# Sheet1.net
KiCad netlist of a schematic drawn in Altium Designer
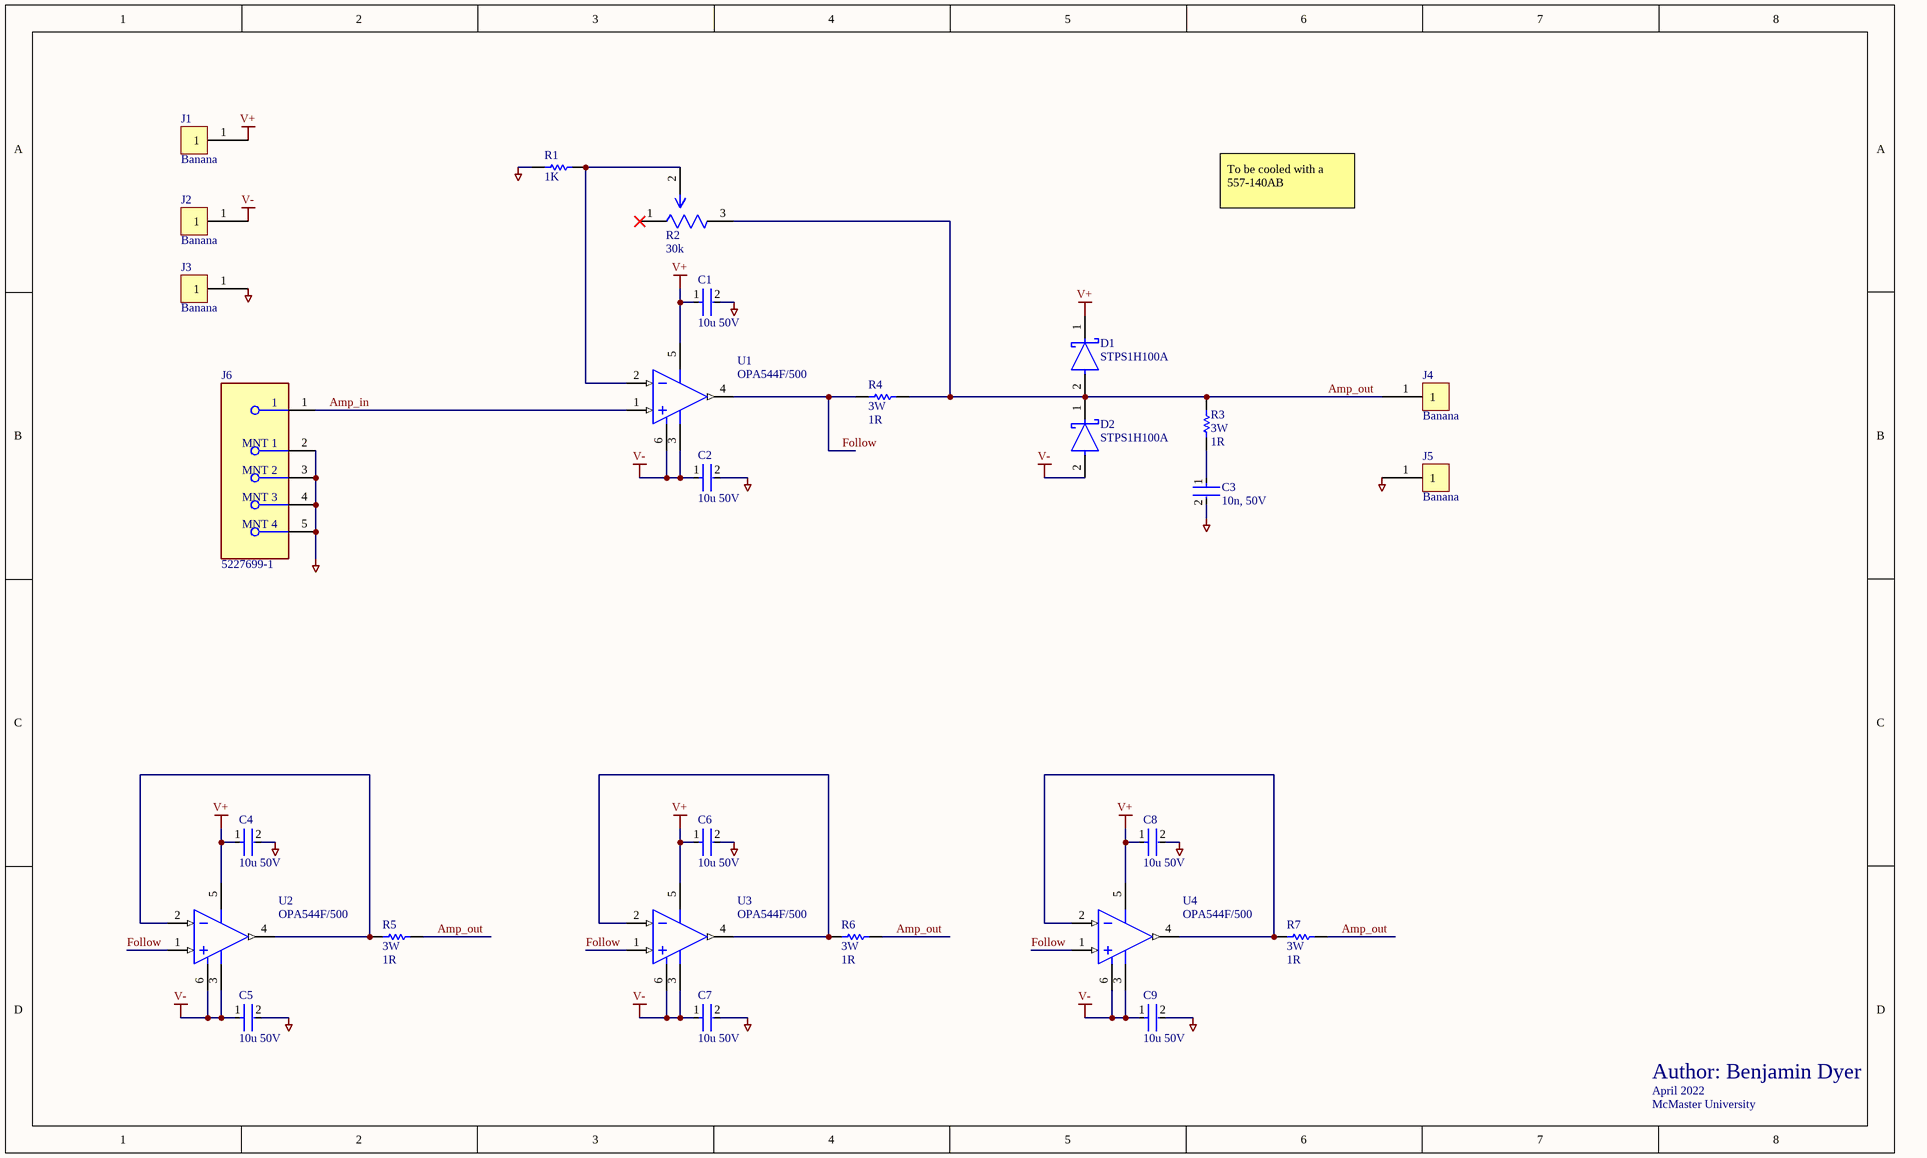
[diagram p0: Sheet1.SchDoc]

(export (version "E")
  (design (tool "Eeschema 10.0.6"))
  (components
    (comp (ref "C1")
      (value "10u 50V")
      (footprint "FP-CL31-IPC_C")
      (description "CAP CER 10UF 50V X5R 1206")
      (fields (field (name "TOLERANCE") "10%") (field (name "MANUFACTURER") "Samsung"))
      (libsource (lib "Altium Content Vault") (part "11868f565c42a9108669ba33697ecf6"))
    )
    (comp (ref "C2")
      (value "10u 50V")
      (footprint "FP-CL31-IPC_C")
      (description "CAP CER 10UF 50V X5R 1206")
      (fields (field (name "TOLERANCE") "10%") (field (name "MANUFACTURER") "Samsung"))
      (libsource (lib "Altium Content Vault") (part "11868f565c42a9108669ba33697ecf6"))
    )
    (comp (ref "C3")
      (value "10n, 50V")
      (footprint "FP-GRM219-0_1-IPC_B")
      (description "Chip Multilayer Ceramic Capacitors for General Purpose, 0805, 10000pF, C0G, 30ppm/°C, 5%, 50V")
      (fields (field (name "VOLTAGE") "50V") (field (name "TOLERANCE") "5%"))
      (libsource (lib "Altium Content Vault") (part "02cd4be3c70576c341d710602a673aa"))
    )
    (comp (ref "C4")
      (value "10u 50V")
      (footprint "FP-CL31-IPC_C")
      (description "CAP CER 10UF 50V X5R 1206")
      (fields (field (name "TOLERANCE") "10%") (field (name "MANUFACTURER") "Samsung"))
      (libsource (lib "Altium Content Vault") (part "11868f565c42a9108669ba33697ecf6"))
    )
    (comp (ref "C5")
      (value "10u 50V")
      (footprint "FP-CL31-IPC_C")
      (description "CAP CER 10UF 50V X5R 1206")
      (fields (field (name "TOLERANCE") "10%") (field (name "MANUFACTURER") "Samsung"))
      (libsource (lib "Altium Content Vault") (part "11868f565c42a9108669ba33697ecf6"))
    )
    (comp (ref "C6")
      (value "10u 50V")
      (footprint "FP-CL31-IPC_C")
      (description "CAP CER 10UF 50V X5R 1206")
      (fields (field (name "TOLERANCE") "10%") (field (name "MANUFACTURER") "Samsung"))
      (libsource (lib "Altium Content Vault") (part "11868f565c42a9108669ba33697ecf6"))
    )
    (comp (ref "C7")
      (value "10u 50V")
      (footprint "FP-CL31-IPC_C")
      (description "CAP CER 10UF 50V X5R 1206")
      (fields (field (name "TOLERANCE") "10%") (field (name "MANUFACTURER") "Samsung"))
      (libsource (lib "Altium Content Vault") (part "11868f565c42a9108669ba33697ecf6"))
    )
    (comp (ref "C8")
      (value "10u 50V")
      (footprint "FP-CL31-IPC_C")
      (description "CAP CER 10UF 50V X5R 1206")
      (fields (field (name "TOLERANCE") "10%") (field (name "MANUFACTURER") "Samsung"))
      (libsource (lib "Altium Content Vault") (part "11868f565c42a9108669ba33697ecf6"))
    )
    (comp (ref "C9")
      (value "10u 50V")
      (footprint "FP-CL31-IPC_C")
      (description "CAP CER 10UF 50V X5R 1206")
      (fields (field (name "TOLERANCE") "10%") (field (name "MANUFACTURER") "Samsung"))
      (libsource (lib "Altium Content Vault") (part "11868f565c42a9108669ba33697ecf6"))
    )
    (comp (ref "D1")
      (value "STPS1H100A")
      (footprint "FP-SMA-MFG")
      (description "DIODE SCHOTTKY 100V 1A SMA")
      (fields
        (field (name "MANUFACTURER") "STMicroelectronics")
        (field (name "OCTOPART") "https://octopart.com/stps1h100a-stmicroelectronics-55399361")
      )
      (libsource (lib "Altium Content Vault") (part "fefb30dabb5d097ae2f038500735429"))
    )
    (comp (ref "D2")
      (value "STPS1H100A")
      (footprint "FP-SMA-MFG")
      (description "DIODE SCHOTTKY 100V 1A SMA")
      (fields
        (field (name "MANUFACTURER") "STMicroelectronics")
        (field (name "OCTOPART") "https://octopart.com/stps1h100a-stmicroelectronics-55399361")
      )
      (libsource (lib "Altium Content Vault") (part "fefb30dabb5d097ae2f038500735429"))
    )
    (comp (ref "J1")
      (value "Banana")
      (footprint "PCBComponent_1")
      (libsource (lib "") (part "Component_1_1"))
    )
    (comp (ref "J2")
      (value "Banana")
      (footprint "PCBComponent_1")
      (libsource (lib "") (part "Component_1_1"))
    )
    (comp (ref "J3")
      (value "Banana")
      (footprint "PCBComponent_1")
      (libsource (lib "") (part "Component_1_1"))
    )
    (comp (ref "J4")
      (value "Banana")
      (footprint "PCBComponent_1")
      (libsource (lib "Schlib1") (part "Component_1"))
    )
    (comp (ref "J5")
      (value "Banana")
      (footprint "PCBComponent_1")
      (libsource (lib "Schlib1") (part "Component_1"))
    )
    (comp (ref "J6")
      (value "5227699-1")
      (footprint "FP-5227699-1-MFG")
      (description "CONN BNC JACK STR 50 OHM PCB")
      (libsource (lib "Altium Content Vault") (part "c65b8a639cdaef1819ea20b5466f8fa"))
    )
    (comp (ref "R1")
      (value "1K")
      (footprint "RESC2013X60X35ML10T20")
      (description "Chip Resistor, 1 KOhm, +/- 1%, 125 mW, -55 to 155 degC, 0805 (2012 Metric), RoHS, Tape and Reel")
      (fields (field (name "TOLERANCE") "1%") (field (name "MANUFACTURER") "Yageo"))
      (libsource (lib "Altium Content Vault") (part "RES-2"))
    )
    (comp (ref "R2")
      (value "30k")
      (footprint "FP-3386F-MFG")
      (description "TRIMMER 30K OHM 0.5W PC PIN TOP")
      (fields (field (name "TOLERANCE") "10%") (field (name "MANUFACTURER PART NUMBER") "3386F-1-303LF"))
      (libsource (lib "Altium Content Vault") (part "f696fc322aeaec4039820165aa0401c"))
    )
    (comp (ref "R3")
      (value "3W")
      (footprint "RESC6332")
      (description "Resistor")
      (fields (field (name "ALTIUM_VALUE") "1R") (field (name "PUBLISHER") "Altium Limited"))
      (libsource (lib "Miscellaneous Devices") (part "Res1"))
    )
    (comp (ref "R4")
      (value "3W")
      (footprint "RESC6332")
      (description "Resistor")
      (fields (field (name "ALTIUM_VALUE") "1R") (field (name "PUBLISHER") "Altium Limited"))
      (libsource (lib "Miscellaneous Devices") (part "Res1"))
    )
    (comp (ref "R5")
      (value "3W")
      (footprint "RESC6332")
      (description "Resistor")
      (fields (field (name "ALTIUM_VALUE") "1R") (field (name "PUBLISHER") "Altium Limited"))
      (libsource (lib "Miscellaneous Devices") (part "Res1"))
    )
    (comp (ref "R6")
      (value "3W")
      (footprint "RESC6332")
      (description "Resistor")
      (fields (field (name "ALTIUM_VALUE") "1R") (field (name "PUBLISHER") "Altium Limited"))
      (libsource (lib "Miscellaneous Devices") (part "Res1"))
    )
    (comp (ref "R7")
      (value "3W")
      (footprint "RESC6332")
      (description "Resistor")
      (fields (field (name "ALTIUM_VALUE") "1R") (field (name "PUBLISHER") "Altium Limited"))
      (libsource (lib "Miscellaneous Devices") (part "Res1"))
    )
    (comp (ref "U1")
      (value "OPA544F/500")
      (footprint "KTT0005A_L")
      (fields (field (name "MANUFACTURER") "Texas Instruments"))
      (libsource (lib "Altium Content Vault") (part "TI-OPA544-KTT5"))
    )
    (comp (ref "U2")
      (value "OPA544F/500")
      (footprint "KTT0005A_L")
      (fields (field (name "MANUFACTURER") "Texas Instruments"))
      (libsource (lib "Altium Content Vault") (part "TI-OPA544-KTT5"))
    )
    (comp (ref "U3")
      (value "OPA544F/500")
      (footprint "KTT0005A_L")
      (fields (field (name "MANUFACTURER") "Texas Instruments"))
      (libsource (lib "Altium Content Vault") (part "TI-OPA544-KTT5"))
    )
    (comp (ref "U4")
      (value "OPA544F/500")
      (footprint "KTT0005A_L")
      (fields (field (name "MANUFACTURER") "Texas Instruments"))
      (libsource (lib "Altium Content Vault") (part "TI-OPA544-KTT5"))
    )
  )
  (nets
    (net (code "1") (name "/Amp_in") (class "Default")
      (node (ref "J6") (pin "1") (pinfunction "1_1") (pintype "passive"))
      (node (ref "U1") (pin "1") (pinfunction "VIN+_1") (pintype "input"))
    )
    (net (code "2") (name "/Amp_out") (class "Default")
      (node (ref "D1") (pin "2") (pinfunction "A_2") (pintype "passive"))
      (node (ref "D2") (pin "1") (pinfunction "K_1") (pintype "passive"))
      (node (ref "J4") (pin "1") (pinfunction "1_1") (pintype "passive"))
      (node (ref "R2") (pin "3") (pinfunction "CW_3") (pintype "passive"))
      (node (ref "R3") (pin "2") (pinfunction "2_2") (pintype "passive"))
      (node (ref "R4") (pin "2") (pinfunction "2_2") (pintype "passive"))
      (node (ref "R5") (pin "2") (pinfunction "2_2") (pintype "passive"))
      (node (ref "R6") (pin "2") (pinfunction "2_2") (pintype "passive"))
      (node (ref "R7") (pin "2") (pinfunction "2_2") (pintype "passive"))
    )
    (net (code "3") (name "/Follow") (class "Default")
      (node (ref "R4") (pin "1") (pinfunction "1_1") (pintype "passive"))
      (node (ref "U1") (pin "4") (pinfunction "VO_4") (pintype "output"))
      (node (ref "U2") (pin "1") (pinfunction "VIN+_1") (pintype "input"))
      (node (ref "U3") (pin "1") (pinfunction "VIN+_1") (pintype "input"))
      (node (ref "U4") (pin "1") (pinfunction "VIN+_1") (pintype "input"))
    )
    (net (code "4") (name "GND") (class "Default")
      (node (ref "C1") (pin "2") (pinfunction "2_2") (pintype "passive"))
      (node (ref "C2") (pin "2") (pinfunction "2_2") (pintype "passive"))
      (node (ref "C3") (pin "2") (pinfunction "2_2") (pintype "passive"))
      (node (ref "C4") (pin "2") (pinfunction "2_2") (pintype "passive"))
      (node (ref "C5") (pin "2") (pinfunction "2_2") (pintype "passive"))
      (node (ref "C6") (pin "2") (pinfunction "2_2") (pintype "passive"))
      (node (ref "C7") (pin "2") (pinfunction "2_2") (pintype "passive"))
      (node (ref "C8") (pin "2") (pinfunction "2_2") (pintype "passive"))
      (node (ref "C9") (pin "2") (pinfunction "2_2") (pintype "passive"))
      (node (ref "J3") (pin "1") (pinfunction "1_1") (pintype "passive"))
      (node (ref "J5") (pin "1") (pinfunction "1_1") (pintype "passive"))
      (node (ref "J6") (pin "2") (pinfunction "MNT_1_2") (pintype "passive"))
      (node (ref "J6") (pin "3") (pinfunction "MNT_2_3") (pintype "passive"))
      (node (ref "J6") (pin "4") (pinfunction "MNT_3_4") (pintype "passive"))
      (node (ref "J6") (pin "5") (pinfunction "MNT_4_5") (pintype "passive"))
      (node (ref "R1") (pin "1") (pinfunction "1_1") (pintype "passive"))
    )
    (net (code "5") (name "Net-(C3-Pad1)") (class "Default")
      (node (ref "C3") (pin "1") (pinfunction "1_1") (pintype "passive"))
      (node (ref "R3") (pin "1") (pinfunction "1_1") (pintype "passive"))
    )
    (net (code "6") (name "Net-(R2-WIPER)") (class "Default")
      (node (ref "R1") (pin "2") (pinfunction "2_2") (pintype "passive"))
      (node (ref "R2") (pin "2") (pinfunction "WIPER_2") (pintype "passive"))
      (node (ref "U1") (pin "2") (pinfunction "VIN-_2") (pintype "input"))
    )
    (net (code "7") (name "Net-(U2-VIN-)") (class "Default")
      (node (ref "R5") (pin "1") (pinfunction "1_1") (pintype "passive"))
      (node (ref "U2") (pin "2") (pinfunction "VIN-_2") (pintype "input"))
      (node (ref "U2") (pin "4") (pinfunction "VO_4") (pintype "output"))
    )
    (net (code "8") (name "Net-(U3-VIN-)") (class "Default")
      (node (ref "R6") (pin "1") (pinfunction "1_1") (pintype "passive"))
      (node (ref "U3") (pin "2") (pinfunction "VIN-_2") (pintype "input"))
      (node (ref "U3") (pin "4") (pinfunction "VO_4") (pintype "output"))
    )
    (net (code "9") (name "Net-(U4-VIN-)") (class "Default")
      (node (ref "R7") (pin "1") (pinfunction "1_1") (pintype "passive"))
      (node (ref "U4") (pin "2") (pinfunction "VIN-_2") (pintype "input"))
      (node (ref "U4") (pin "4") (pinfunction "VO_4") (pintype "output"))
    )
    (net (code "10") (name "V+") (class "Default")
      (node (ref "C1") (pin "1") (pinfunction "1_1") (pintype "passive"))
      (node (ref "C4") (pin "1") (pinfunction "1_1") (pintype "passive"))
      (node (ref "C6") (pin "1") (pinfunction "1_1") (pintype "passive"))
      (node (ref "C8") (pin "1") (pinfunction "1_1") (pintype "passive"))
      (node (ref "D1") (pin "1") (pinfunction "K_1") (pintype "passive"))
      (node (ref "J1") (pin "1") (pinfunction "1_1") (pintype "passive"))
      (node (ref "U1") (pin "5") (pinfunction "V+_5") (pintype "power_in"))
      (node (ref "U2") (pin "5") (pinfunction "V+_5") (pintype "power_in"))
      (node (ref "U3") (pin "5") (pinfunction "V+_5") (pintype "power_in"))
      (node (ref "U4") (pin "5") (pinfunction "V+_5") (pintype "power_in"))
    )
    (net (code "11") (name "V-") (class "Default")
      (node (ref "C2") (pin "1") (pinfunction "1_1") (pintype "passive"))
      (node (ref "C5") (pin "1") (pinfunction "1_1") (pintype "passive"))
      (node (ref "C7") (pin "1") (pinfunction "1_1") (pintype "passive"))
      (node (ref "C9") (pin "1") (pinfunction "1_1") (pintype "passive"))
      (node (ref "D2") (pin "2") (pinfunction "A_2") (pintype "passive"))
      (node (ref "J2") (pin "1") (pinfunction "1_1") (pintype "passive"))
      (node (ref "U1") (pin "3") (pinfunction "V-_3") (pintype "power_in"))
      (node (ref "U1") (pin "6") (pinfunction "EP_6") (pintype "power_in"))
      (node (ref "U2") (pin "3") (pinfunction "V-_3") (pintype "power_in"))
      (node (ref "U2") (pin "6") (pinfunction "EP_6") (pintype "power_in"))
      (node (ref "U3") (pin "3") (pinfunction "V-_3") (pintype "power_in"))
      (node (ref "U3") (pin "6") (pinfunction "EP_6") (pintype "power_in"))
      (node (ref "U4") (pin "3") (pinfunction "V-_3") (pintype "power_in"))
      (node (ref "U4") (pin "6") (pinfunction "EP_6") (pintype "power_in"))
    )
    (net (code "12") (name "unconnected-(R2-CCW-Pad1)") (class "Default")
      (node (ref "R2") (pin "1") (pinfunction "CCW_1") (pintype "passive+no_connect"))
    )
  )
)
